# Scheme_VHF-Unit.net
KiCad netlist of a schematic drawn in Altium Designer
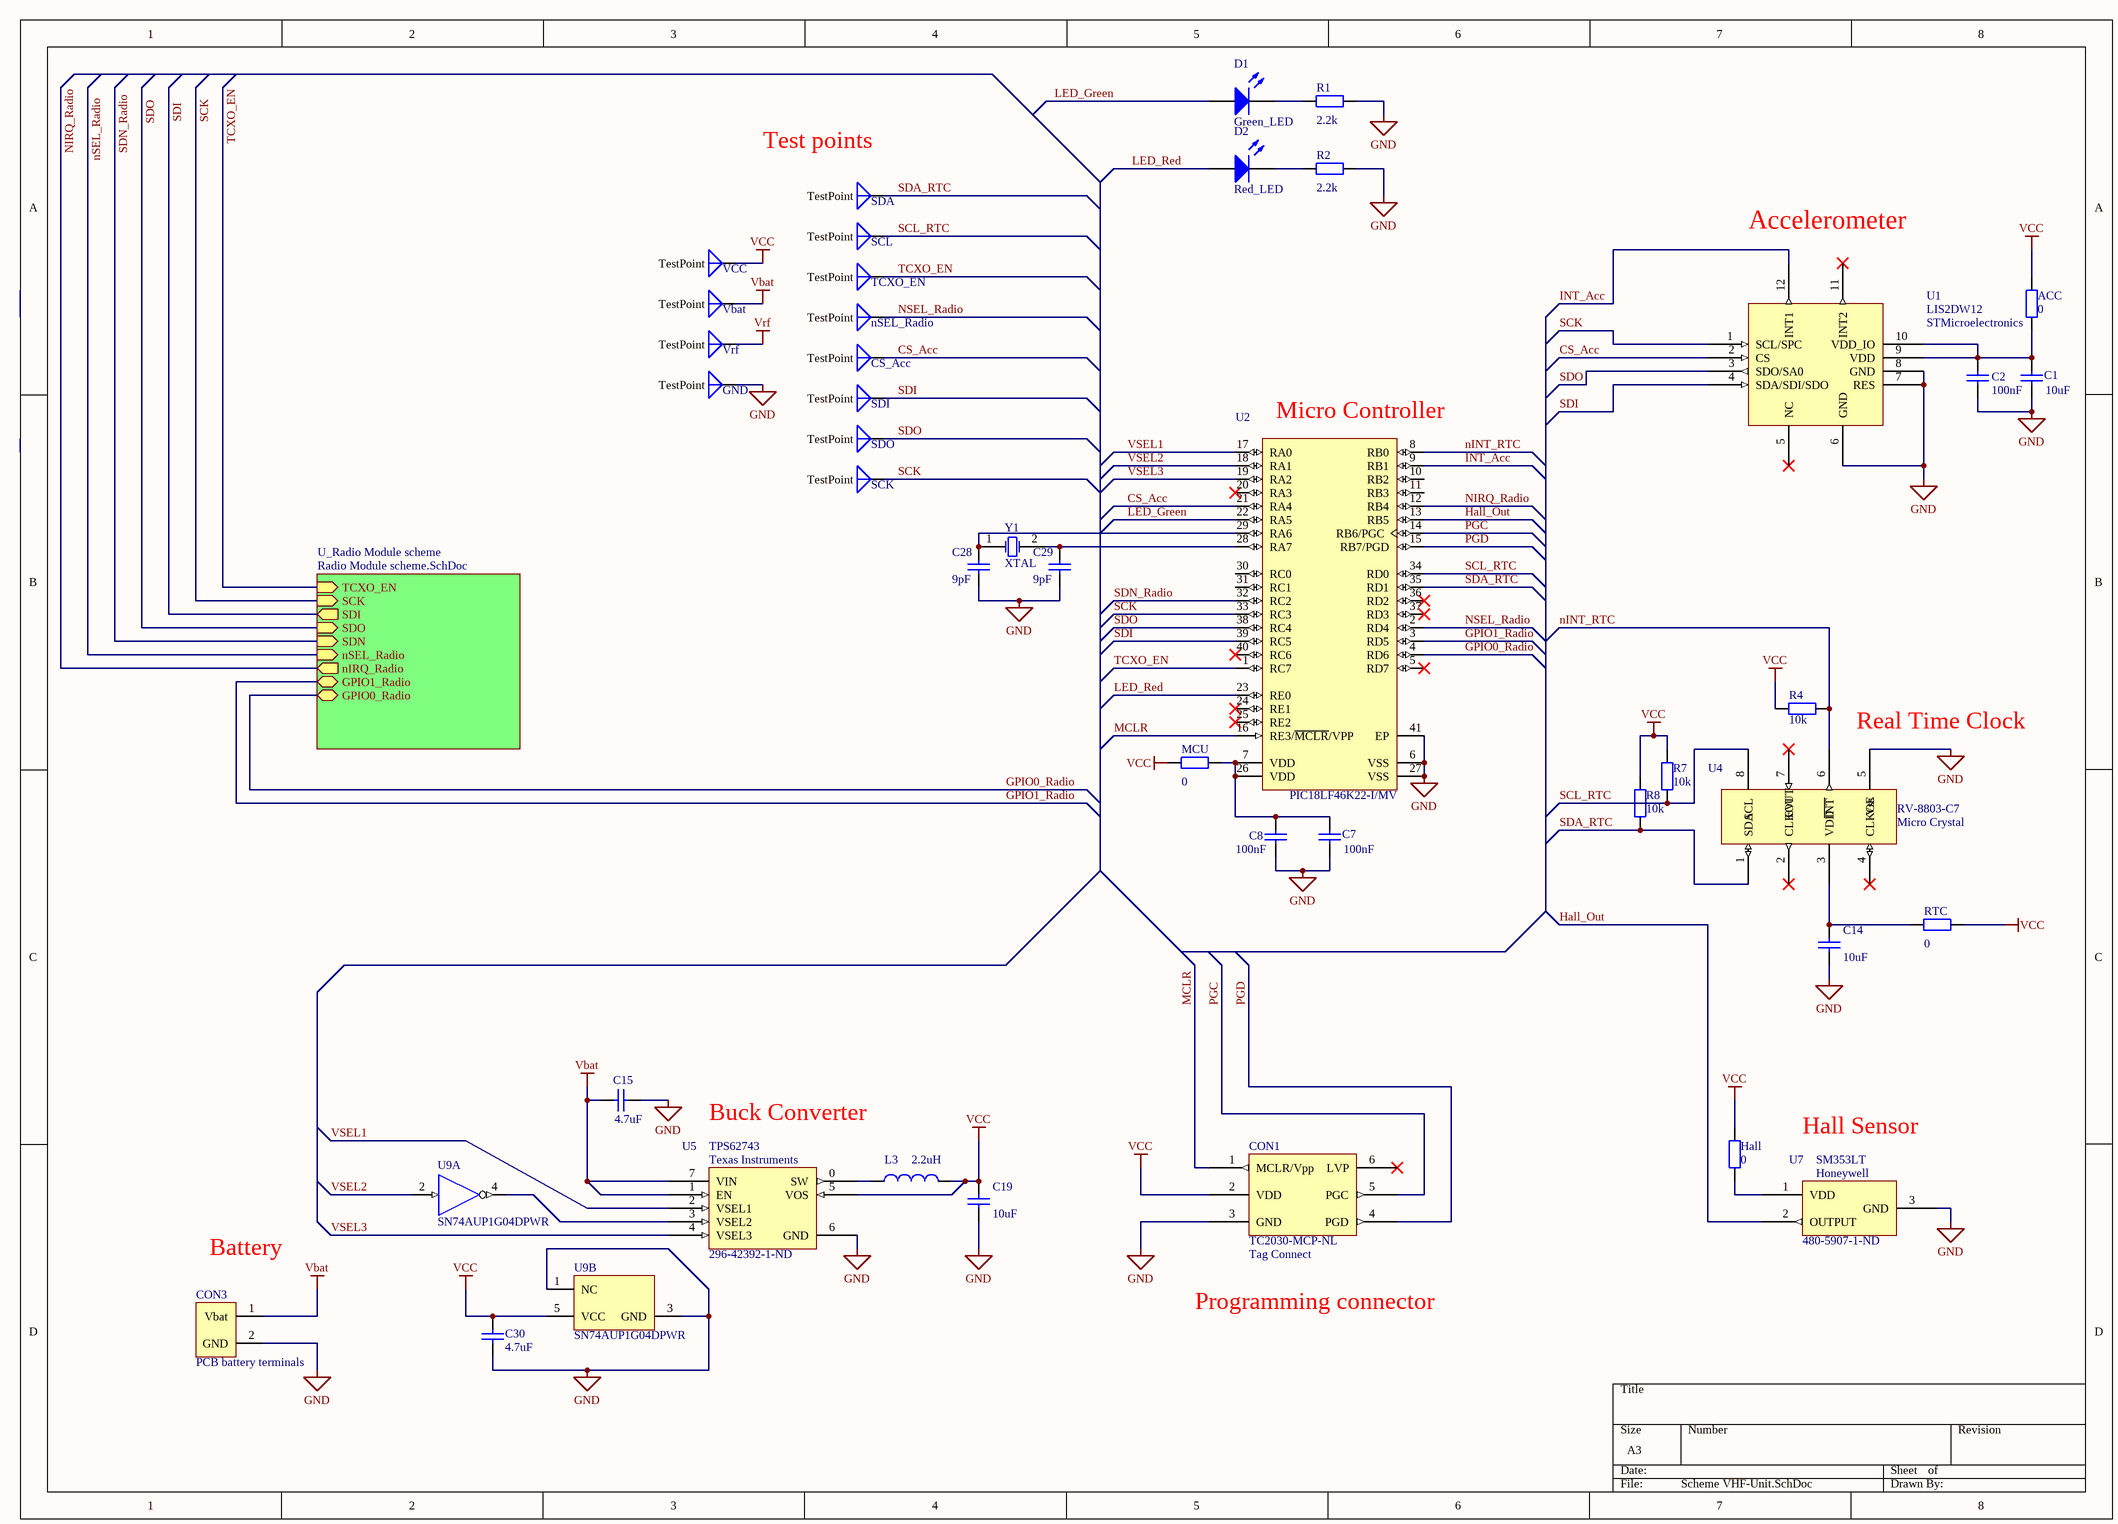
[diagram p0: Scheme VHF-Unit.SchDoc]

(export (version "E")
  (design (tool "Eeschema 10.0.6"))
  (components
    (comp (ref "ACC")
      (value "0")
      (footprint "0402_SMD_RES_0_Ohm")
      (description "Resistor")
      (fields (field (name "Comment") "Res2") (field (name "PUBLISHER") "Altium Limited"))
      (libsource (lib "") (part "Res2_1"))
    )
    (comp (ref "C1")
      (value "10uF")
      (footprint "0402_CAP")
      (description "Capacitor (Semiconductor SIM Model)")
      (fields (field (name "PUBLISHER") "Altium Limited"))
      (libsource (lib "Miscellaneous Devices") (part "Cap Semi"))
    )
    (comp (ref "C2")
      (value "100nF")
      (footprint "0402_CAP")
      (description "Capacitor (Semiconductor SIM Model)")
      (fields (field (name "PUBLISHER") "Altium Limited"))
      (libsource (lib "Miscellaneous Devices") (part "Cap Semi"))
    )
    (comp (ref "C7")
      (value "100nF")
      (footprint "0402_CAP")
      (description "Capacitor (Semiconductor SIM Model)")
      (fields (field (name "Comment") "Cap Semi") (field (name "PUBLISHER") "Altium Limited"))
      (libsource (lib "Miscellaneous Devices") (part "Cap Semi"))
    )
    (comp (ref "C8")
      (value "100nF")
      (footprint "0402_CAP")
      (description "Capacitor (Semiconductor SIM Model)")
      (fields (field (name "Comment") "Cap Semi") (field (name "PUBLISHER") "Altium Limited"))
      (libsource (lib "Miscellaneous Devices") (part "Cap Semi"))
    )
    (comp (ref "C14")
      (value "10uF")
      (footprint "0402_CAP")
      (description "Capacitor (Semiconductor SIM Model)")
      (fields (field (name "Comment") "Cap Semi") (field (name "PUBLISHER") "Altium Limited"))
      (libsource (lib "Miscellaneous Devices") (part "Cap Semi"))
    )
    (comp (ref "C15")
      (value "4.7uF")
      (footprint "0402_CAP")
      (description "Capacitor (Semiconductor SIM Model)")
      (fields (field (name "Comment") "Cap Semi") (field (name "PUBLISHER") "Altium Limited"))
      (libsource (lib "Miscellaneous Devices") (part "Cap Semi"))
    )
    (comp (ref "C19")
      (value "10uF")
      (footprint "0402_CAP")
      (description "Capacitor (Semiconductor SIM Model)")
      (fields (field (name "Comment") "Cap Semi") (field (name "PUBLISHER") "Altium Limited"))
      (libsource (lib "Miscellaneous Devices") (part "Cap Semi"))
    )
    (comp (ref "C28")
      (value "9pF")
      (footprint "0402_CAP")
      (description "Capacitor (Semiconductor SIM Model)")
      (fields (field (name "Comment") "Cap Semi") (field (name "PUBLISHER") "Altium Limited"))
      (libsource (lib "Miscellaneous Devices") (part "Cap Semi"))
    )
    (comp (ref "C29")
      (value "9pF")
      (footprint "0402_CAP")
      (description "Capacitor (Semiconductor SIM Model)")
      (fields (field (name "Comment") "Cap Semi") (field (name "PUBLISHER") "Altium Limited"))
      (libsource (lib "Miscellaneous Devices") (part "Cap Semi"))
    )
    (comp (ref "C30")
      (value "4.7uF")
      (footprint "0402_CAP")
      (description "Capacitor (Semiconductor SIM Model)")
      (fields (field (name "Comment") "Cap Semi") (field (name "PUBLISHER") "Altium Limited"))
      (libsource (lib "Miscellaneous Devices") (part "Cap Semi"))
    )
    (comp (ref "CON1")
      (value "TC2030-MCP-NL")
      (footprint "TAG-CONNECT")
      (description "Tag Connect programming connector")
      (fields (field (name "MFR 1") "Tag Connect"))
      (libsource (lib "TC2030-MCP-NL") (part "TC2030-MCP-NL"))
    )
    (comp (ref "CON3")
      (value "PCB battery terminals")
      (footprint "JST-PH")
      (description "2 pin Battery Connectors")
      (libsource (lib "Battery-Connector") (part "Battery connenctor"))
    )
    (comp (ref "CS_Acc")
      (value "Antenna")
      (footprint "TestPoint")
      (description "Testpoint connector")
      (libsource (lib "TestPoint") (part "TestPoint"))
    )
    (comp (ref "D1")
      (value "Green_LED")
      (footprint "0603_LED")
      (description "Typical RED, GREEN, YELLOW, AMBER GaAs LED")
      (fields (field (name "PUBLISHER") "Altium Limited"))
      (libsource (lib "Miscellaneous Devices") (part "LED2"))
    )
    (comp (ref "D2")
      (value "Red_LED")
      (footprint "0603_LED")
      (description "Typical RED, GREEN, YELLOW, AMBER GaAs LED")
      (fields (field (name "PUBLISHER") "Altium Limited"))
      (libsource (lib "Miscellaneous Devices") (part "LED2"))
    )
    (comp (ref "GND")
      (value "Antenna")
      (footprint "TestPoint")
      (description "Testpoint connector")
      (libsource (lib "TestPoint") (part "TestPoint"))
    )
    (comp (ref "Hall")
      (value "0")
      (footprint "0402_SMD_RES_0_Ohm")
      (description "Resistor")
      (fields (field (name "Comment") "Res2") (field (name "PUBLISHER") "Altium Limited"))
      (libsource (lib "") (part "Res2_1"))
    )
    (comp (ref "L3")
      (value "2.2uH")
      (footprint "0402_CAP")
      (description "Inductor")
      (fields (field (name "PUBLISHER") "Altium Limited"))
      (libsource (lib "Miscellaneous Devices") (part "Inductor"))
    )
    (comp (ref "MCU")
      (value "0")
      (footprint "0402_SMD_RES_0_Ohm")
      (description "Resistor")
      (fields (field (name "Comment") "Res2") (field (name "PUBLISHER") "Altium Limited"))
      (libsource (lib "Miscellaneous Devices") (part "Res2"))
    )
    (comp (ref "nSEL_Radio")
      (value "Antenna")
      (footprint "TestPoint")
      (description "Testpoint connector")
      (libsource (lib "TestPoint") (part "TestPoint"))
    )
    (comp (ref "R1")
      (value "2.2k")
      (footprint "0402_RES")
      (description "Resistor")
      (fields (field (name "Comment") "Res2") (field (name "PUBLISHER") "Altium Limited"))
      (libsource (lib "Miscellaneous Devices") (part "Res2"))
    )
    (comp (ref "R2")
      (value "2.2k")
      (footprint "0402_RES")
      (description "Resistor")
      (fields (field (name "Comment") "Res2") (field (name "PUBLISHER") "Altium Limited"))
      (libsource (lib "Miscellaneous Devices") (part "Res2"))
    )
    (comp (ref "R4")
      (value "10k")
      (footprint "0402_RES")
      (description "Resistor")
      (fields (field (name "Comment") "Res2") (field (name "PUBLISHER") "Altium Limited"))
      (libsource (lib "Miscellaneous Devices") (part "Res2"))
    )
    (comp (ref "R7")
      (value "10k")
      (footprint "0402_RES")
      (description "Resistor")
      (fields (field (name "Comment") "Res2") (field (name "PUBLISHER") "Altium Limited"))
      (libsource (lib "") (part "Res2_1"))
    )
    (comp (ref "R8")
      (value "10k")
      (footprint "0402_RES")
      (description "Resistor")
      (fields (field (name "Comment") "Res2") (field (name "PUBLISHER") "Altium Limited"))
      (libsource (lib "") (part "Res2_1"))
    )
    (comp (ref "RTC")
      (value "0")
      (footprint "0402_SMD_RES_0_Ohm")
      (description "Resistor")
      (fields (field (name "Comment") "Res2") (field (name "PUBLISHER") "Altium Limited"))
      (libsource (lib "Miscellaneous Devices") (part "Res2"))
    )
    (comp (ref "SCK")
      (value "Antenna")
      (footprint "TestPoint")
      (description "Testpoint connector")
      (libsource (lib "TestPoint") (part "TestPoint"))
    )
    (comp (ref "SCL")
      (value "Antenna")
      (footprint "TestPoint")
      (description "Testpoint connector")
      (libsource (lib "TestPoint") (part "TestPoint"))
    )
    (comp (ref "SDA")
      (value "Antenna")
      (footprint "TestPoint")
      (description "Testpoint connector")
      (libsource (lib "TestPoint") (part "TestPoint"))
    )
    (comp (ref "SDI")
      (value "Antenna")
      (footprint "TestPoint")
      (description "Testpoint connector")
      (libsource (lib "TestPoint") (part "TestPoint"))
    )
    (comp (ref "SDO")
      (value "Antenna")
      (footprint "TestPoint")
      (description "Testpoint connector")
      (libsource (lib "TestPoint") (part "TestPoint"))
    )
    (comp (ref "TCXO_EN")
      (value "Antenna")
      (footprint "TestPoint")
      (description "Testpoint connector")
      (libsource (lib "TestPoint") (part "TestPoint"))
    )
    (comp (ref "U1")
      (value "LIS2DW12")
      (footprint "LGA12C50P4X4_200X200X70 Low Density")
      (description "Digital output motion sensor 3-axis")
      (fields (field (name "MFR 1") "STMicroelectronics"))
      (libsource (lib "LIS2DW12") (part "LIS2DW12"))
    )
    (comp (ref "U2")
      (value "PIC18LF46K22-I/MV")
      (footprint "MCHP-UQFN-MV40_M")
      (fields (field (name "MANUFACTURER") "Microchip"))
      (libsource (lib "Microchip PIC18") (part "PIC18LF46K22-I/MV"))
    )
    (comp (ref "U4")
      (value "RV-8803-C7")
      (footprint "LGA8C90P4X2_320X150X80")
      (fields (field (name "MFR 1") "Micro Crystal"))
      (libsource (lib "RV-8803-C7") (part "RV-8803-C7"))
    )
    (comp (ref "U5")
      (value "TPS62743")
      (footprint "BGA8C40P2X4_87X156X50")
      (description "High EfficiencyBuck Converterwith Ultra-lowQuiescentCurrent")
      (fields
        (field (name "MFR 1") "Texas Instruments")
        (field (name "SUPPLIER PART NUMBER 1") "296-42392-1-ND")
      )
      (libsource (lib "TPS62743") (part "TPS62743"))
    )
    (comp (ref "U7")
      (value "SM353LT")
      (footprint "SOT95P280X140-3N")
      (description "Magnetoresistive Sensor ICs")
      (fields (field (name "MFR 1") "Honeywell") (field (name "SUPPLIER PART NUMBER 1") "480-5907-1-ND"))
      (libsource (lib "SM353LT") (part "SM353LT"))
    )
    (comp (ref "U9")
      (value "SN74AUP1G04DPWR")
      (footprint "DSF0006A_V")
      (description "Low-Power Single Inverter Gate, DPW0004A, LARGE T&R")
      (fields
        (field (name "GENERIC PART NUMBER") "SN74AUP1G04")
        (field (name "MANUFACTURER") "Texas Instruments")
      )
      (libsource (lib "TI_Logic_Little_Logic") (part "SN74AUP1G04DPWR"))
    )
    (comp (ref "Vbat")
      (value "Antenna")
      (footprint "TestPoint")
      (description "Testpoint connector")
      (libsource (lib "TestPoint") (part "TestPoint"))
    )
    (comp (ref "VCC")
      (value "Antenna")
      (footprint "TestPoint")
      (description "Testpoint connector")
      (libsource (lib "TestPoint") (part "TestPoint"))
    )
    (comp (ref "Vrf")
      (value "Antenna")
      (footprint "TestPoint")
      (description "Testpoint connector")
      (libsource (lib "TestPoint") (part "TestPoint"))
    )
    (comp (ref "Y1")
      (value "XTAL")
      (footprint "ABS05-XTAL")
      (description "Crystal Oscillator")
      (fields (field (name "PUBLISHER") "Altium Limited"))
      (libsource (lib "Miscellaneous Devices") (part "XTAL"))
    )
  )
  (nets
    (net (code "1") (name "/CS_Acc") (class "Default")
      (node (ref "CS_Acc") (pin "1") (pinfunction "TestPoint_1") (pintype "passive"))
      (node (ref "U1") (pin "2") (pinfunction "CS_2") (pintype "input"))
      (node (ref "U2") (pin "21") (pinfunction "RA4_21") (pintype "bidirectional"))
    )
    (net (code "2") (name "/GPIO0_Radio") (class "Default")
      (node (ref "U2") (pin "4") (pinfunction "RD6_4") (pintype "bidirectional"))
    )
    (net (code "3") (name "/GPIO1_Radio") (class "Default")
      (node (ref "U2") (pin "3") (pinfunction "RD5_3") (pintype "bidirectional"))
    )
    (net (code "4") (name "/Hall_Out") (class "Default")
      (node (ref "U2") (pin "13") (pinfunction "RB5_13") (pintype "bidirectional"))
      (node (ref "U7") (pin "2") (pinfunction "OUTPUT_2") (pintype "output"))
    )
    (net (code "5") (name "/INT_Acc") (class "Default")
      (node (ref "U1") (pin "12") (pinfunction "INT1_12") (pintype "output"))
      (node (ref "U2") (pin "9") (pinfunction "RB1_9") (pintype "bidirectional"))
    )
    (net (code "6") (name "/LED_Green") (class "Default")
      (node (ref "D1") (pin "1") (pinfunction "A_1") (pintype "passive"))
      (node (ref "U2") (pin "22") (pinfunction "RA5_22") (pintype "bidirectional"))
    )
    (net (code "7") (name "/LED_Red") (class "Default")
      (node (ref "D2") (pin "1") (pinfunction "A_1") (pintype "passive"))
      (node (ref "U2") (pin "23") (pinfunction "RE0_23") (pintype "bidirectional"))
    )
    (net (code "8") (name "/MCLR") (class "Default")
      (node (ref "CON1") (pin "1") (pinfunction "MCLR/Vpp_1") (pintype "output"))
      (node (ref "U2") (pin "16") (pinfunction "RE3/~{MCLR}/VPP_16") (pintype "input"))
    )
    (net (code "9") (name "/NIRQ_Radio") (class "Default")
      (node (ref "U2") (pin "12") (pinfunction "RB4_12") (pintype "bidirectional"))
    )
    (net (code "10") (name "/NSEL_Radio") (class "Default")
      (node (ref "U2") (pin "2") (pinfunction "RD4_2") (pintype "bidirectional"))
      (node (ref "nSEL_Radio") (pin "1") (pinfunction "TestPoint_1") (pintype "passive"))
    )
    (net (code "11") (name "/PGC") (class "Default")
      (node (ref "CON1") (pin "5") (pinfunction "PGC_5") (pintype "output"))
      (node (ref "U2") (pin "14") (pinfunction "RB6/PGC_14") (pintype "bidirectional"))
    )
    (net (code "12") (name "/PGD") (class "Default")
      (node (ref "CON1") (pin "4") (pinfunction "PGD_4") (pintype "output"))
      (node (ref "U2") (pin "15") (pinfunction "RB7/PGD_15") (pintype "bidirectional"))
    )
    (net (code "13") (name "/SCK") (class "Default")
      (node (ref "SCK") (pin "1") (pinfunction "TestPoint_1") (pintype "passive"))
      (node (ref "U1") (pin "1") (pinfunction "SCL/SPC_1") (pintype "input"))
      (node (ref "U2") (pin "33") (pinfunction "RC3_33") (pintype "bidirectional"))
    )
    (net (code "14") (name "/SCL_RTC") (class "Default")
      (node (ref "R7") (pin "1") (pinfunction "1_1") (pintype "passive"))
      (node (ref "SCL") (pin "1") (pinfunction "TestPoint_1") (pintype "passive"))
      (node (ref "U2") (pin "34") (pinfunction "RD0_34") (pintype "bidirectional"))
      (node (ref "U4") (pin "8") (pinfunction "SCL_8") (pintype "passive"))
    )
    (net (code "15") (name "/SDA_RTC") (class "Default")
      (node (ref "R8") (pin "1") (pinfunction "1_1") (pintype "passive"))
      (node (ref "SDA") (pin "1") (pinfunction "TestPoint_1") (pintype "passive"))
      (node (ref "U2") (pin "35") (pinfunction "RD1_35") (pintype "bidirectional"))
      (node (ref "U4") (pin "1") (pinfunction "SDA_1") (pintype "bidirectional"))
    )
    (net (code "16") (name "/SDI") (class "Default")
      (node (ref "SDI") (pin "1") (pinfunction "TestPoint_1") (pintype "passive"))
      (node (ref "U1") (pin "4") (pinfunction "SDA/SDI/SDO_4") (pintype "input"))
      (node (ref "U2") (pin "39") (pinfunction "RC5_39") (pintype "bidirectional"))
    )
    (net (code "17") (name "/SDN_Radio") (class "Default")
      (node (ref "U2") (pin "32") (pinfunction "RC2_32") (pintype "bidirectional"))
    )
    (net (code "18") (name "/SDO") (class "Default")
      (node (ref "SDO") (pin "1") (pinfunction "TestPoint_1") (pintype "passive"))
      (node (ref "U1") (pin "3") (pinfunction "SDO/SA0_3") (pintype "output"))
      (node (ref "U2") (pin "38") (pinfunction "RC4_38") (pintype "bidirectional"))
    )
    (net (code "19") (name "/TCXO_EN") (class "Default")
      (node (ref "TCXO_EN") (pin "1") (pinfunction "TestPoint_1") (pintype "passive"))
      (node (ref "U2") (pin "1") (pinfunction "RC7_1") (pintype "bidirectional"))
    )
    (net (code "20") (name "/VSEL1") (class "Default")
      (node (ref "U2") (pin "17") (pinfunction "RA0_17") (pintype "bidirectional"))
      (node (ref "U5") (pin "2") (pinfunction "VSEL1_2") (pintype "input"))
    )
    (net (code "21") (name "/VSEL2") (class "Default")
      (node (ref "U2") (pin "18") (pinfunction "RA1_18") (pintype "bidirectional"))
      (node (ref "U9") (pin "2") (pinfunction "A_2") (pintype "input"))
    )
    (net (code "22") (name "/VSEL3") (class "Default")
      (node (ref "U2") (pin "19") (pinfunction "RA2_19") (pintype "bidirectional"))
      (node (ref "U5") (pin "4") (pinfunction "VSEL3_4") (pintype "input"))
    )
    (net (code "23") (name "/nINT_RTC") (class "Default")
      (node (ref "R4") (pin "2") (pinfunction "2_2") (pintype "passive"))
      (node (ref "U2") (pin "8") (pinfunction "RB0_8") (pintype "bidirectional"))
      (node (ref "U4") (pin "6") (pinfunction "~{INT}_6") (pintype "output"))
    )
    (net (code "25") (name "GND") (class "Default")
      (node (ref "C1") (pin "1") (pinfunction "1_1") (pintype "passive"))
      (node (ref "C14") (pin "1") (pinfunction "1_1") (pintype "passive"))
      (node (ref "C15") (pin "1") (pinfunction "1_1") (pintype "passive"))
      (node (ref "C19") (pin "1") (pinfunction "1_1") (pintype "passive"))
      (node (ref "C2") (pin "1") (pinfunction "1_1") (pintype "passive"))
      (node (ref "C28") (pin "1") (pinfunction "1_1") (pintype "passive"))
      (node (ref "C29") (pin "1") (pinfunction "1_1") (pintype "passive"))
      (node (ref "C30") (pin "1") (pinfunction "1_1") (pintype "passive"))
      (node (ref "C7") (pin "1") (pinfunction "1_1") (pintype "passive"))
      (node (ref "C8") (pin "1") (pinfunction "1_1") (pintype "passive"))
      (node (ref "CON1") (pin "3") (pinfunction "GND_3") (pintype "power_in"))
      (node (ref "CON3") (pin "2") (pinfunction "GND_2") (pintype "passive"))
      (node (ref "GND") (pin "1") (pinfunction "TestPoint_1") (pintype "passive"))
      (node (ref "R1") (pin "2") (pinfunction "2_2") (pintype "passive"))
      (node (ref "R2") (pin "2") (pinfunction "2_2") (pintype "passive"))
      (node (ref "U1") (pin "6") (pinfunction "GND_6") (pintype "power_in"))
      (node (ref "U1") (pin "7") (pinfunction "RES_7") (pintype "passive"))
      (node (ref "U1") (pin "8") (pinfunction "GND_8") (pintype "power_in"))
      (node (ref "U2") (pin "27") (pinfunction "VSS_27") (pintype "power_in"))
      (node (ref "U2") (pin "41") (pinfunction "EP_41") (pintype "passive"))
      (node (ref "U2") (pin "6") (pinfunction "VSS_6") (pintype "power_in"))
      (node (ref "U4") (pin "5") (pinfunction "Vss_5") (pintype "power_in"))
      (node (ref "U5") (pin "6") (pinfunction "GND_6") (pintype "power_in"))
      (node (ref "U7") (pin "3") (pinfunction "GND_3") (pintype "power_in"))
      (node (ref "U9") (pin "1") (pinfunction "NC_1") (pintype "passive"))
      (node (ref "U9") (pin "3") (pinfunction "GND_3") (pintype "power_in"))
    )
    (net (code "26") (name "Net-(C7-Pad2)") (class "Default")
      (node (ref "C7") (pin "2") (pinfunction "2_2") (pintype "passive"))
      (node (ref "C8") (pin "2") (pinfunction "2_2") (pintype "passive"))
      (node (ref "MCU") (pin "2") (pinfunction "2_2") (pintype "passive"))
      (node (ref "U2") (pin "26") (pinfunction "VDD_26") (pintype "power_in"))
      (node (ref "U2") (pin "7") (pinfunction "VDD_7") (pintype "power_in"))
    )
    (net (code "27") (name "Net-(D1-K)") (class "Default")
      (node (ref "D1") (pin "2") (pinfunction "K_2") (pintype "passive"))
      (node (ref "R1") (pin "1") (pinfunction "1_1") (pintype "passive"))
    )
    (net (code "28") (name "Net-(D2-K)") (class "Default")
      (node (ref "D2") (pin "2") (pinfunction "K_2") (pintype "passive"))
      (node (ref "R2") (pin "1") (pinfunction "1_1") (pintype "passive"))
    )
    (net (code "29") (name "Net-(U1-VDD)") (class "Default")
      (node (ref "ACC") (pin "1") (pinfunction "1_1") (pintype "passive"))
      (node (ref "C1") (pin "2") (pinfunction "2_2") (pintype "passive"))
      (node (ref "C2") (pin "2") (pinfunction "2_2") (pintype "passive"))
      (node (ref "U1") (pin "10") (pinfunction "VDD_IO_10") (pintype "power_in"))
      (node (ref "U1") (pin "9") (pinfunction "VDD_9") (pintype "power_in"))
    )
    (net (code "30") (name "Net-(U2-RA6)") (class "Default")
      (node (ref "C28") (pin "2") (pinfunction "2_2") (pintype "passive"))
      (node (ref "U2") (pin "29") (pinfunction "RA6_29") (pintype "bidirectional"))
      (node (ref "Y1") (pin "1") (pinfunction "OSC1_1") (pintype "passive"))
    )
    (net (code "31") (name "Net-(U2-RA7)") (class "Default")
      (node (ref "C29") (pin "2") (pinfunction "2_2") (pintype "passive"))
      (node (ref "U2") (pin "28") (pinfunction "RA7_28") (pintype "bidirectional"))
      (node (ref "Y1") (pin "2") (pinfunction "OSC2_2") (pintype "passive"))
    )
    (net (code "32") (name "Net-(U4-VDD)") (class "Default")
      (node (ref "C14") (pin "2") (pinfunction "2_2") (pintype "passive"))
      (node (ref "RTC") (pin "1") (pinfunction "1_1") (pintype "passive"))
      (node (ref "U4") (pin "3") (pinfunction "VDD_3") (pintype "power_in"))
    )
    (net (code "33") (name "Net-(U5-SW)") (class "Default")
      (node (ref "L3") (pin "1") (pinfunction "1_1") (pintype "passive"))
      (node (ref "U5") (pin "0") (pinfunction "SW_0") (pintype "output"))
    )
    (net (code "34") (name "Net-(U5-VSEL2)") (class "Default")
      (node (ref "U5") (pin "3") (pinfunction "VSEL2_3") (pintype "input"))
      (node (ref "U9") (pin "4") (pinfunction "Y_4") (pintype "output"))
    )
    (net (code "35") (name "Net-(U7-VDD)") (class "Default")
      (node (ref "Hall") (pin "1") (pinfunction "1_1") (pintype "passive"))
      (node (ref "U7") (pin "1") (pinfunction "VDD_1") (pintype "power_in"))
    )
    (net (code "36") (name "VCC") (class "Default")
      (node (ref "ACC") (pin "2") (pinfunction "2_2") (pintype "passive"))
      (node (ref "C19") (pin "2") (pinfunction "2_2") (pintype "passive"))
      (node (ref "C30") (pin "2") (pinfunction "2_2") (pintype "passive"))
      (node (ref "CON1") (pin "2") (pinfunction "VDD_2") (pintype "passive"))
      (node (ref "Hall") (pin "2") (pinfunction "2_2") (pintype "passive"))
      (node (ref "L3") (pin "2") (pinfunction "2_2") (pintype "passive"))
      (node (ref "MCU") (pin "1") (pinfunction "1_1") (pintype "passive"))
      (node (ref "R4") (pin "1") (pinfunction "1_1") (pintype "passive"))
      (node (ref "R7") (pin "2") (pinfunction "2_2") (pintype "passive"))
      (node (ref "R8") (pin "2") (pinfunction "2_2") (pintype "passive"))
      (node (ref "RTC") (pin "2") (pinfunction "2_2") (pintype "passive"))
      (node (ref "U5") (pin "5") (pinfunction "VOS_5") (pintype "input"))
      (node (ref "U9") (pin "5") (pinfunction "VCC_5") (pintype "power_in"))
      (node (ref "VCC") (pin "1") (pinfunction "TestPoint_1") (pintype "passive"))
    )
    (net (code "37") (name "Vbat") (class "Default")
      (node (ref "C15") (pin "2") (pinfunction "2_2") (pintype "passive"))
      (node (ref "CON3") (pin "1") (pinfunction "Vbat_1") (pintype "passive"))
      (node (ref "U5") (pin "1") (pinfunction "EN_1") (pintype "input"))
      (node (ref "U5") (pin "7") (pinfunction "VIN_7") (pintype "power_in"))
      (node (ref "Vbat") (pin "1") (pinfunction "TestPoint_1") (pintype "passive"))
    )
    (net (code "38") (name "Vrf") (class "Default")
      (node (ref "Vrf") (pin "1") (pinfunction "TestPoint_1") (pintype "passive"))
    )
    (net (code "39") (name "unconnected-(CON1-LVP-Pad6)") (class "Default")
      (node (ref "CON1") (pin "6") (pinfunction "LVP_6") (pintype "passive+no_connect"))
    )
    (net (code "40") (name "unconnected-(U1-INT2-Pad11)") (class "Default")
      (node (ref "U1") (pin "11") (pinfunction "INT2_11") (pintype "output+no_connect"))
    )
    (net (code "41") (name "unconnected-(U1-NC-Pad5)") (class "Default")
      (node (ref "U1") (pin "5") (pinfunction "NC_5") (pintype "passive+no_connect"))
    )
    (net (code "42") (name "unconnected-(U2-RA3-Pad20)") (class "Default")
      (node (ref "U2") (pin "20") (pinfunction "RA3_20") (pintype "bidirectional+no_connect"))
    )
    (net (code "43") (name "unconnected-(U2-RB2-Pad10)") (class "Default")
      (node (ref "U2") (pin "10") (pinfunction "RB2_10") (pintype "bidirectional"))
    )
    (net (code "44") (name "unconnected-(U2-RB3-Pad11)") (class "Default")
      (node (ref "U2") (pin "11") (pinfunction "RB3_11") (pintype "bidirectional"))
    )
    (net (code "45") (name "unconnected-(U2-RC0-Pad30)") (class "Default")
      (node (ref "U2") (pin "30") (pinfunction "RC0_30") (pintype "bidirectional"))
    )
    (net (code "46") (name "unconnected-(U2-RC1-Pad31)") (class "Default")
      (node (ref "U2") (pin "31") (pinfunction "RC1_31") (pintype "bidirectional"))
    )
    (net (code "47") (name "unconnected-(U2-RC6-Pad40)") (class "Default")
      (node (ref "U2") (pin "40") (pinfunction "RC6_40") (pintype "bidirectional+no_connect"))
    )
    (net (code "48") (name "unconnected-(U2-RD2-Pad36)") (class "Default")
      (node (ref "U2") (pin "36") (pinfunction "RD2_36") (pintype "bidirectional+no_connect"))
    )
    (net (code "49") (name "unconnected-(U2-RD3-Pad37)") (class "Default")
      (node (ref "U2") (pin "37") (pinfunction "RD3_37") (pintype "bidirectional+no_connect"))
    )
    (net (code "50") (name "unconnected-(U2-RD7-Pad5)") (class "Default")
      (node (ref "U2") (pin "5") (pinfunction "RD7_5") (pintype "bidirectional+no_connect"))
    )
    (net (code "51") (name "unconnected-(U2-RE1-Pad24)") (class "Default")
      (node (ref "U2") (pin "24") (pinfunction "RE1_24") (pintype "bidirectional+no_connect"))
    )
    (net (code "52") (name "unconnected-(U2-RE2-Pad25)") (class "Default")
      (node (ref "U2") (pin "25") (pinfunction "RE2_25") (pintype "bidirectional+no_connect"))
    )
    (net (code "53") (name "unconnected-(U4-CLKOE-Pad4)") (class "Default")
      (node (ref "U4") (pin "4") (pinfunction "CLKOE_4") (pintype "bidirectional+no_connect"))
    )
    (net (code "54") (name "unconnected-(U4-CLKOUT-Pad2)") (class "Default")
      (node (ref "U4") (pin "2") (pinfunction "CLKOUT_2") (pintype "output+no_connect"))
    )
    (net (code "55") (name "unconnected-(U4-EVI-Pad7)") (class "Default")
      (node (ref "U4") (pin "7") (pinfunction "EVI_7") (pintype "input+no_connect"))
    )
  )
)
